# YaskawaSpeedControl.net
KiCad netlist of a schematic drawn in EAGLE
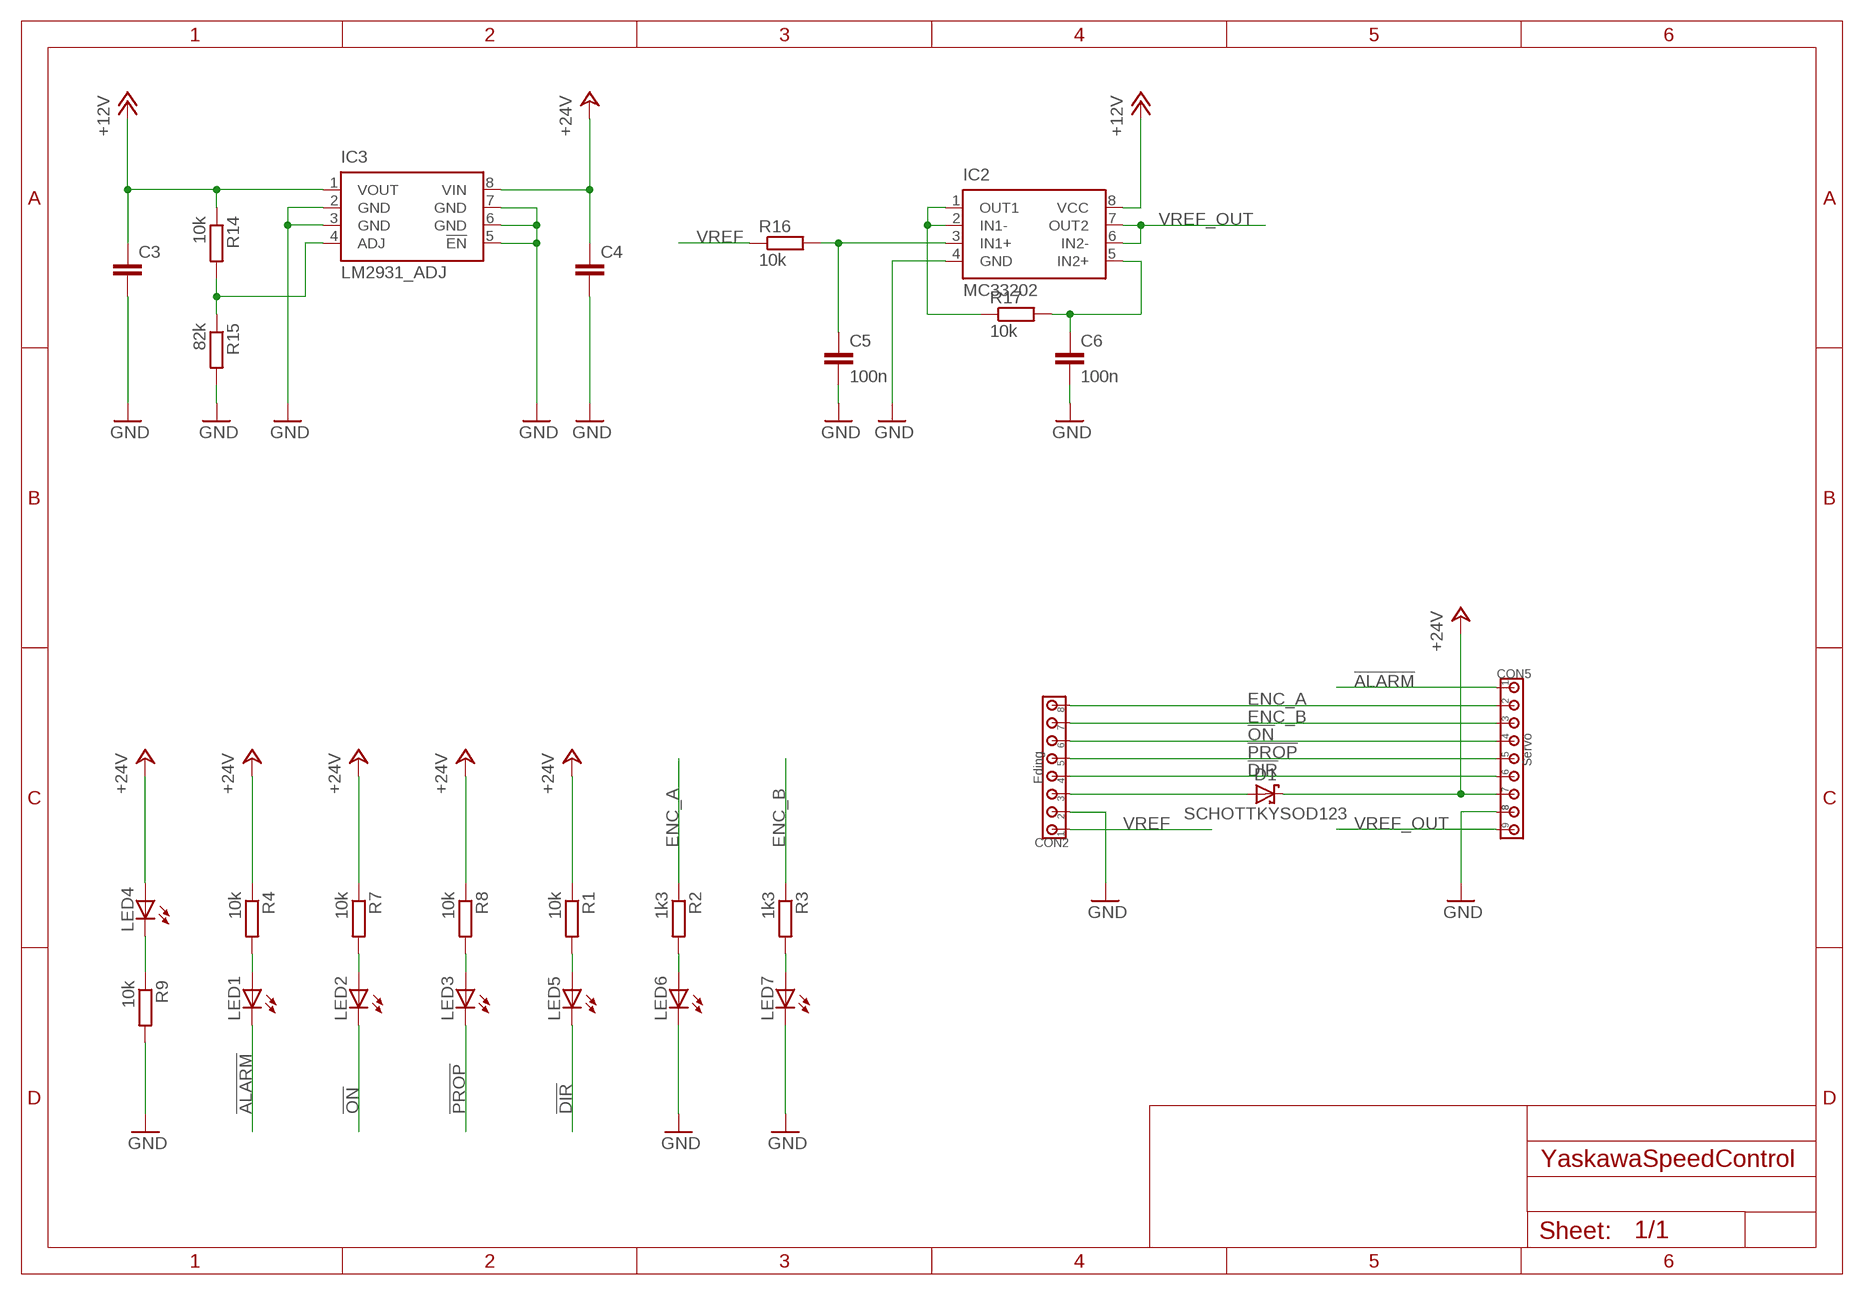
[diagram p0: schematic, sheet 1]

(export (version "E")
  (design (tool "Eeschema 10.0.6"))
  (components
    (comp (ref "C3")
      (value "CC1206")
      (footprint "eagle-import:C1206")
      (libsource (lib "eagle-import") (part "CC1206"))
    )
    (comp (ref "C4")
      (value "CC1206")
      (footprint "eagle-import:C1206")
      (libsource (lib "eagle-import") (part "CC1206"))
    )
    (comp (ref "C5")
      (value "100n")
      (footprint "eagle-import:C0805")
      (libsource (lib "eagle-import") (part "CC0805"))
    )
    (comp (ref "C6")
      (value "100n")
      (footprint "eagle-import:C0805")
      (libsource (lib "eagle-import") (part "CC0805"))
    )
    (comp (ref "CON2")
      (value "Eding")
      (footprint "eagle-import:3.5MM_8X")
      (libsource (lib "eagle-import") (part "CON_8X3.5MM"))
    )
    (comp (ref "CON5")
      (value "Servo")
      (footprint "eagle-import:3.5MM_9X")
      (libsource (lib "eagle-import") (part "CON_9X3.5MM"))
    )
    (comp (ref "D1")
      (value "SCHOTTKYSOD123")
      (footprint "eagle-import:SOD123")
      (libsource (lib "eagle-import") (part "SCHOTTKYSOD123"))
    )
    (comp (ref "IC2")
      (value "MC33202")
      (footprint "eagle-import:SOIC8")
      (libsource (lib "eagle-import") (part "MC33202"))
    )
    (comp (ref "IC3")
      (value "LM2931_ADJ")
      (footprint "eagle-import:SOIC8")
      (libsource (lib "eagle-import") (part "LM2931_ADJ"))
    )
    (comp (ref "LED1")
      (value "LED0805")
      (footprint "eagle-import:LED0805")
      (libsource (lib "eagle-import") (part "LED0805"))
    )
    (comp (ref "LED2")
      (value "LED0805")
      (footprint "eagle-import:LED0805")
      (libsource (lib "eagle-import") (part "LED0805"))
    )
    (comp (ref "LED3")
      (value "LED0805")
      (footprint "eagle-import:LED0805")
      (libsource (lib "eagle-import") (part "LED0805"))
    )
    (comp (ref "LED4")
      (value "LED0805")
      (footprint "eagle-import:LED0805")
      (libsource (lib "eagle-import") (part "LED0805"))
    )
    (comp (ref "LED5")
      (value "LED0805")
      (footprint "eagle-import:LED0805")
      (libsource (lib "eagle-import") (part "LED0805"))
    )
    (comp (ref "LED6")
      (value "LED0805")
      (footprint "eagle-import:LED0805")
      (libsource (lib "eagle-import") (part "LED0805"))
    )
    (comp (ref "LED7")
      (value "LED0805")
      (footprint "eagle-import:LED0805")
      (libsource (lib "eagle-import") (part "LED0805"))
    )
    (comp (ref "R1")
      (value "10k")
      (footprint "eagle-import:R0805")
      (libsource (lib "eagle-import") (part "RESISTORR0805"))
    )
    (comp (ref "R2")
      (value "1k3")
      (footprint "eagle-import:R0805")
      (libsource (lib "eagle-import") (part "RESISTORR0805"))
    )
    (comp (ref "R3")
      (value "1k3")
      (footprint "eagle-import:R0805")
      (libsource (lib "eagle-import") (part "RESISTORR0805"))
    )
    (comp (ref "R4")
      (value "10k")
      (footprint "eagle-import:R0805")
      (libsource (lib "eagle-import") (part "RESISTORR0805"))
    )
    (comp (ref "R7")
      (value "10k")
      (footprint "eagle-import:R0805")
      (libsource (lib "eagle-import") (part "RESISTORR0805"))
    )
    (comp (ref "R8")
      (value "10k")
      (footprint "eagle-import:R0805")
      (libsource (lib "eagle-import") (part "RESISTORR0805"))
    )
    (comp (ref "R9")
      (value "10k")
      (footprint "eagle-import:R0805")
      (libsource (lib "eagle-import") (part "RESISTORR0805"))
    )
    (comp (ref "R14")
      (value "10k")
      (footprint "eagle-import:R0805")
      (libsource (lib "eagle-import") (part "RESISTORR0805"))
    )
    (comp (ref "R15")
      (value "82k")
      (footprint "eagle-import:R0805")
      (libsource (lib "eagle-import") (part "RESISTORR0805"))
    )
    (comp (ref "R16")
      (value "10k")
      (footprint "eagle-import:R0805")
      (libsource (lib "eagle-import") (part "RESISTORR0805"))
    )
    (comp (ref "R17")
      (value "10k")
      (footprint "eagle-import:R0805")
      (libsource (lib "eagle-import") (part "RESISTORR0805"))
    )
  )
  (nets
    (net (code "1") (name "+12V") (class "Default")
      (node (ref "C3") (pin "1") (pinfunction "1_1") (pintype "passive"))
      (node (ref "IC2") (pin "8") (pinfunction "VCC_8") (pintype "input"))
      (node (ref "IC3") (pin "1") (pinfunction "VOUT_1") (pintype "output"))
      (node (ref "R14") (pin "1") (pinfunction "1_1") (pintype "passive"))
    )
    (net (code "2") (name "+24V") (class "Default")
      (node (ref "C4") (pin "1") (pinfunction "1_1") (pintype "passive"))
      (node (ref "CON5") (pin "7") (pinfunction "P$7_7") (pintype "passive"))
      (node (ref "D1") (pin "C") (pinfunction "C_C") (pintype "passive"))
      (node (ref "IC3") (pin "8") (pinfunction "VIN_8") (pintype "passive"))
      (node (ref "LED4") (pin "A") (pinfunction "A_A") (pintype "passive"))
      (node (ref "R1") (pin "1") (pinfunction "1_1") (pintype "passive"))
      (node (ref "R4") (pin "1") (pinfunction "1_1") (pintype "passive"))
      (node (ref "R7") (pin "1") (pinfunction "1_1") (pintype "passive"))
      (node (ref "R8") (pin "1") (pinfunction "1_1") (pintype "passive"))
    )
    (net (code "3") (name "/ENC_A") (class "Default")
      (node (ref "CON2") (pin "8") (pinfunction "P$8_8") (pintype "passive"))
      (node (ref "CON5") (pin "2") (pinfunction "P$2_2") (pintype "passive"))
      (node (ref "R2") (pin "1") (pinfunction "1_1") (pintype "passive"))
    )
    (net (code "4") (name "/ENC_B") (class "Default")
      (node (ref "CON2") (pin "7") (pinfunction "P$7_7") (pintype "passive"))
      (node (ref "CON5") (pin "3") (pinfunction "P$3_3") (pintype "passive"))
      (node (ref "R3") (pin "1") (pinfunction "1_1") (pintype "passive"))
    )
    (net (code "5") (name "/VREF") (class "Default")
      (node (ref "CON2") (pin "1") (pinfunction "P$1_1") (pintype "passive"))
      (node (ref "R16") (pin "1") (pinfunction "1_1") (pintype "passive"))
    )
    (net (code "6") (name "/VREF_OUT") (class "Default")
      (node (ref "CON5") (pin "9") (pinfunction "P$9_9") (pintype "passive"))
      (node (ref "IC2") (pin "6") (pinfunction "IN2-_6") (pintype "passive"))
      (node (ref "IC2") (pin "7") (pinfunction "OUT2_7") (pintype "input"))
    )
    (net (code "7") (name "/~{ALARM}") (class "Default")
      (node (ref "CON5") (pin "1") (pinfunction "P$1_1") (pintype "passive"))
      (node (ref "LED1") (pin "C") (pinfunction "C_C") (pintype "passive"))
    )
    (net (code "8") (name "/~{DIR}") (class "Default")
      (node (ref "CON2") (pin "4") (pinfunction "P$4_4") (pintype "passive"))
      (node (ref "CON5") (pin "6") (pinfunction "P$6_6") (pintype "passive"))
      (node (ref "LED5") (pin "C") (pinfunction "C_C") (pintype "passive"))
    )
    (net (code "9") (name "/~{ON}") (class "Default")
      (node (ref "CON2") (pin "6") (pinfunction "P$6_6") (pintype "passive"))
      (node (ref "CON5") (pin "4") (pinfunction "P$4_4") (pintype "passive"))
      (node (ref "LED2") (pin "C") (pinfunction "C_C") (pintype "passive"))
    )
    (net (code "10") (name "/~{PROP}") (class "Default")
      (node (ref "CON2") (pin "5") (pinfunction "P$5_5") (pintype "passive"))
      (node (ref "CON5") (pin "5") (pinfunction "P$5_5") (pintype "passive"))
      (node (ref "LED3") (pin "C") (pinfunction "C_C") (pintype "passive"))
    )
    (net (code "11") (name "GND") (class "Default")
      (node (ref "C3") (pin "2") (pinfunction "2_2") (pintype "passive"))
      (node (ref "C4") (pin "2") (pinfunction "2_2") (pintype "passive"))
      (node (ref "C5") (pin "2") (pinfunction "2_2") (pintype "passive"))
      (node (ref "C6") (pin "2") (pinfunction "2_2") (pintype "passive"))
      (node (ref "CON2") (pin "2") (pinfunction "P$2_2") (pintype "passive"))
      (node (ref "CON5") (pin "8") (pinfunction "P$8_8") (pintype "passive"))
      (node (ref "IC2") (pin "4") (pinfunction "GND_4") (pintype "power_in"))
      (node (ref "IC3") (pin "2") (pinfunction "GND_2") (pintype "passive"))
      (node (ref "IC3") (pin "3") (pinfunction "GND_3") (pintype "passive"))
      (node (ref "IC3") (pin "5") (pinfunction "~{EN}_5") (pintype "passive"))
      (node (ref "IC3") (pin "6") (pinfunction "GND_6") (pintype "output"))
      (node (ref "IC3") (pin "7") (pinfunction "GND_7") (pintype "output"))
      (node (ref "LED6") (pin "C") (pinfunction "C_C") (pintype "passive"))
      (node (ref "LED7") (pin "C") (pinfunction "C_C") (pintype "passive"))
      (node (ref "R15") (pin "2") (pinfunction "2_2") (pintype "passive"))
      (node (ref "R9") (pin "2") (pinfunction "2_2") (pintype "passive"))
    )
    (net (code "12") (name "Net-(CON2-P$3)") (class "Default")
      (node (ref "CON2") (pin "3") (pinfunction "P$3_3") (pintype "passive"))
      (node (ref "D1") (pin "A") (pinfunction "A_A") (pintype "passive"))
    )
    (net (code "13") (name "Net-(IC2-IN1+)") (class "Default")
      (node (ref "C5") (pin "1") (pinfunction "1_1") (pintype "passive"))
      (node (ref "IC2") (pin "3") (pinfunction "IN1+_3") (pintype "input"))
      (node (ref "R16") (pin "2") (pinfunction "2_2") (pintype "passive"))
    )
    (net (code "14") (name "Net-(IC2-IN1-)") (class "Default")
      (node (ref "IC2") (pin "1") (pinfunction "OUT1_1") (pintype "input"))
      (node (ref "IC2") (pin "2") (pinfunction "IN1-_2") (pintype "input"))
      (node (ref "R17") (pin "1") (pinfunction "1_1") (pintype "passive"))
    )
    (net (code "15") (name "Net-(IC2-IN2+)") (class "Default")
      (node (ref "C6") (pin "1") (pinfunction "1_1") (pintype "passive"))
      (node (ref "IC2") (pin "5") (pinfunction "IN2+_5") (pintype "passive"))
      (node (ref "R17") (pin "2") (pinfunction "2_2") (pintype "passive"))
    )
    (net (code "16") (name "Net-(IC3-ADJ)") (class "Default")
      (node (ref "IC3") (pin "4") (pinfunction "ADJ_4") (pintype "output"))
      (node (ref "R14") (pin "2") (pinfunction "2_2") (pintype "passive"))
      (node (ref "R15") (pin "1") (pinfunction "1_1") (pintype "passive"))
    )
    (net (code "17") (name "Net-(LED1-PadA)") (class "Default")
      (node (ref "LED1") (pin "A") (pinfunction "A_A") (pintype "passive"))
      (node (ref "R4") (pin "2") (pinfunction "2_2") (pintype "passive"))
    )
    (net (code "18") (name "Net-(LED2-PadA)") (class "Default")
      (node (ref "LED2") (pin "A") (pinfunction "A_A") (pintype "passive"))
      (node (ref "R7") (pin "2") (pinfunction "2_2") (pintype "passive"))
    )
    (net (code "19") (name "Net-(LED3-PadA)") (class "Default")
      (node (ref "LED3") (pin "A") (pinfunction "A_A") (pintype "passive"))
      (node (ref "R8") (pin "2") (pinfunction "2_2") (pintype "passive"))
    )
    (net (code "20") (name "Net-(LED4-PadC)") (class "Default")
      (node (ref "LED4") (pin "C") (pinfunction "C_C") (pintype "passive"))
      (node (ref "R9") (pin "1") (pinfunction "1_1") (pintype "passive"))
    )
    (net (code "21") (name "Net-(LED5-PadA)") (class "Default")
      (node (ref "LED5") (pin "A") (pinfunction "A_A") (pintype "passive"))
      (node (ref "R1") (pin "2") (pinfunction "2_2") (pintype "passive"))
    )
    (net (code "22") (name "Net-(LED6-PadA)") (class "Default")
      (node (ref "LED6") (pin "A") (pinfunction "A_A") (pintype "passive"))
      (node (ref "R2") (pin "2") (pinfunction "2_2") (pintype "passive"))
    )
    (net (code "23") (name "Net-(LED7-PadA)") (class "Default")
      (node (ref "LED7") (pin "A") (pinfunction "A_A") (pintype "passive"))
      (node (ref "R3") (pin "2") (pinfunction "2_2") (pintype "passive"))
    )
  )
)
